# 1-Schematic_polaris_3_3_copy.net
KiCad netlist of a schematic drawn in EasyEDA
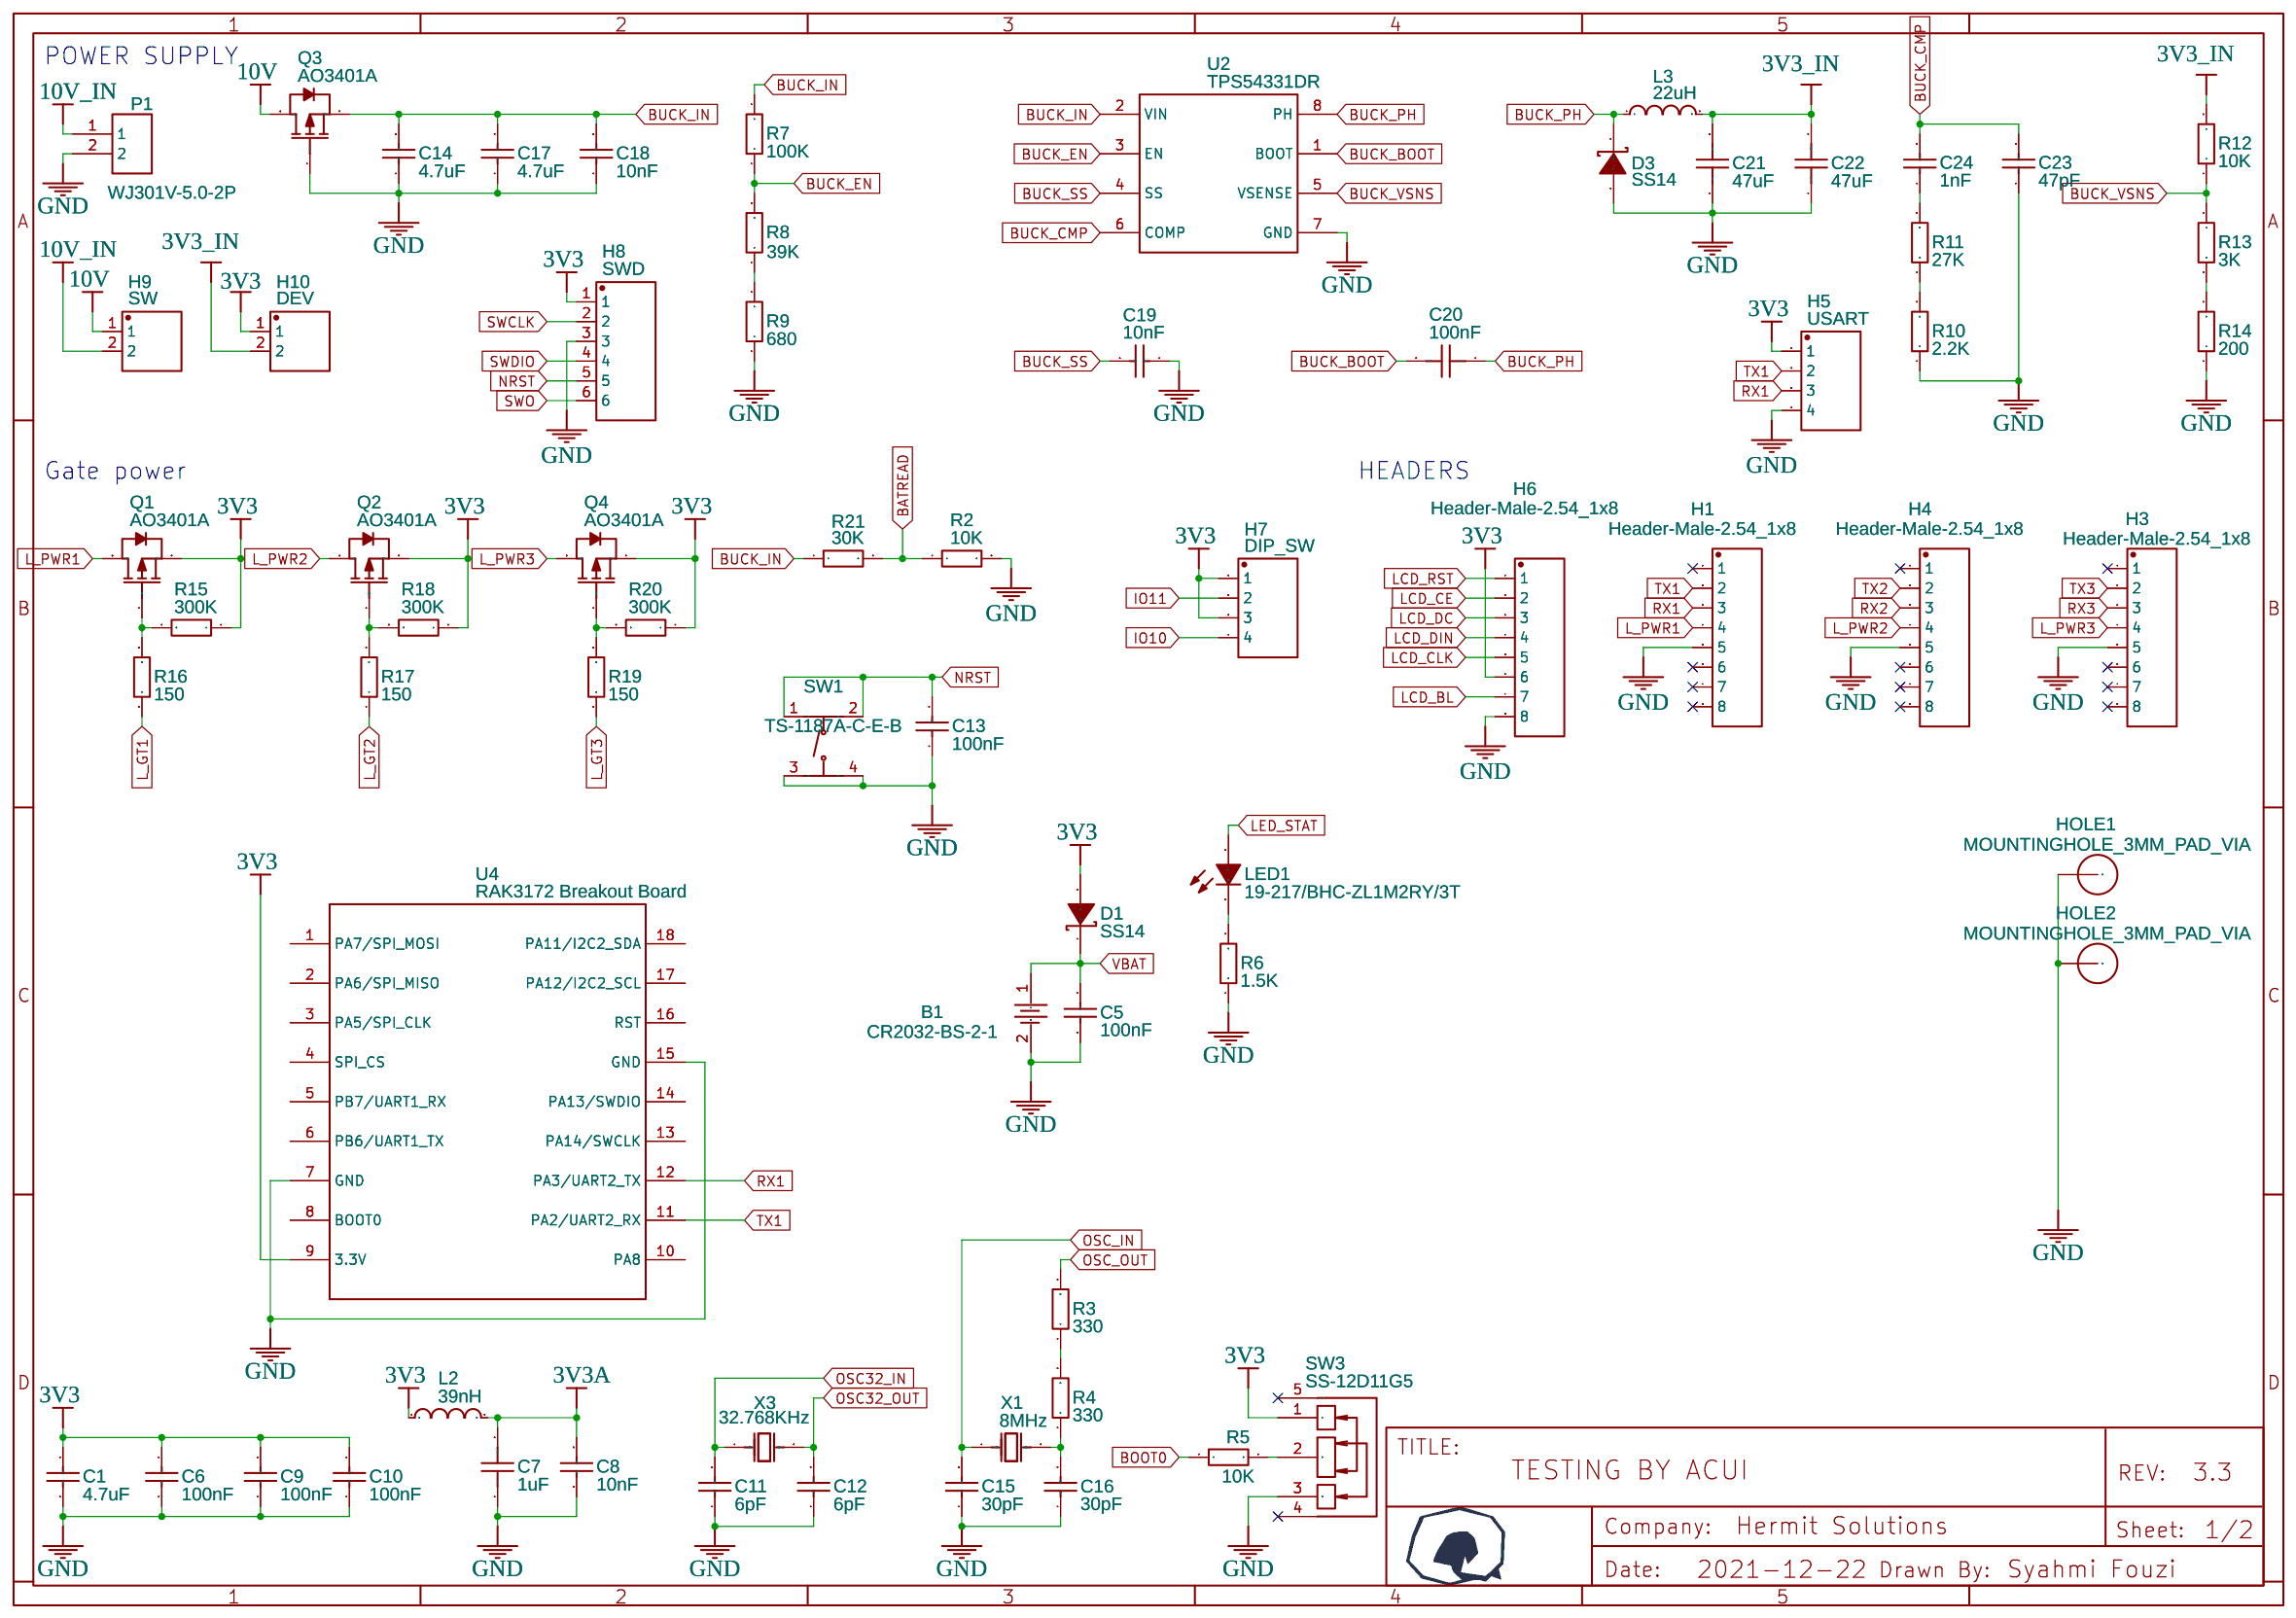
[diagram p0: S_3.3_1.2 copy]
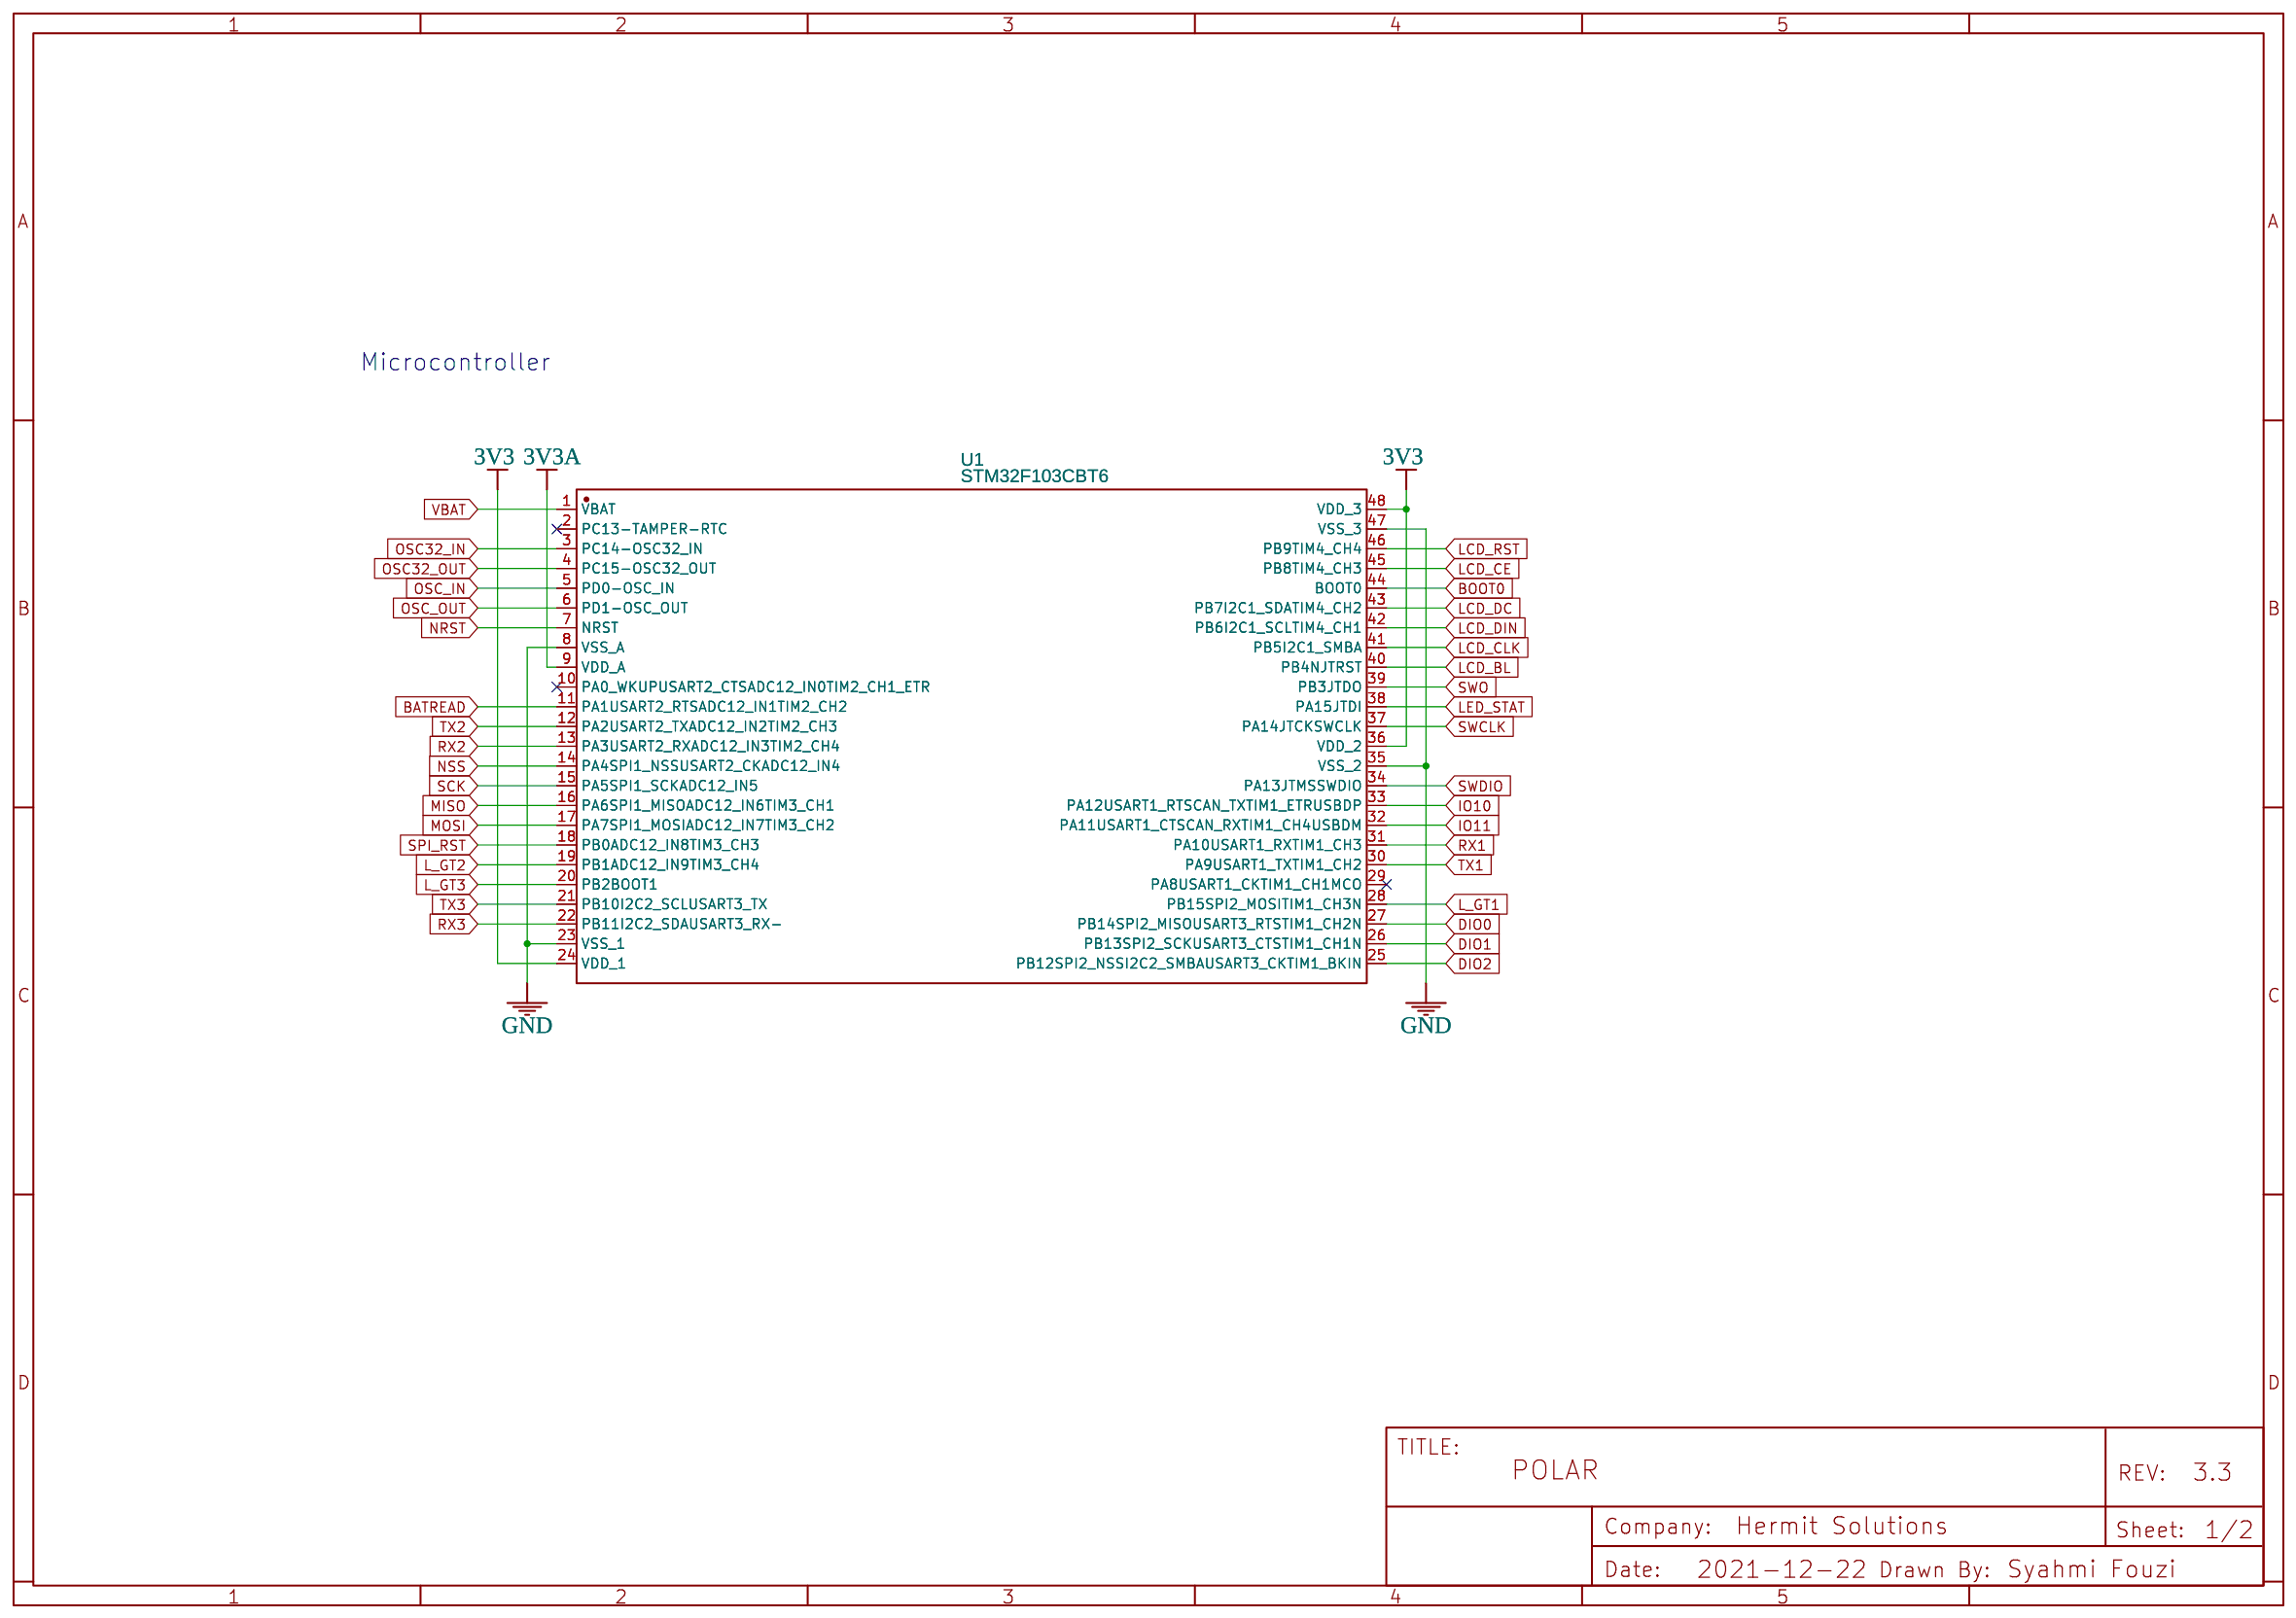
[diagram p1: S_3.3_2.2 copy]

(export (version "E")
  (design (tool "Eeschema 10.0.6"))
  (components
    (comp (ref "B1")
      (value "CR2032-BS-2-1")
      (fields (field (name "BOM_Manufacturer Part") "BS-2-1") (field (name "BOM_Supplier Part") "C70376"))
      (libsource (lib "") (part "CR2032-BS-2-1"))
    )
    (comp (ref "C1")
      (value "4.7uF")
      (fields
        (field (name "BOM_Manufacturer Part") "CL10A475KO8NNNC")
        (field (name "BOM_Supplier Part") "C19666")
      )
      (libsource (lib "") (part "CL10A475KO8NNNC"))
    )
    (comp (ref "C5")
      (value "100nF")
      (fields
        (field (name "BOM_Manufacturer Part") "CC0805KRX7R9BB104")
        (field (name "BOM_Supplier Part") "C49678")
      )
      (libsource (lib "") (part "CC0805KRX7R9BB104"))
    )
    (comp (ref "C6")
      (value "100nF")
      (fields
        (field (name "BOM_Manufacturer Part") "CL05B104KO5NNNC")
        (field (name "BOM_Supplier Part") "C1525")
      )
      (libsource (lib "") (part "CL05B104KO5NNNC"))
    )
    (comp (ref "C7")
      (value "1uF")
      (fields
        (field (name "BOM_Manufacturer Part") "CL05A105KA5NQNC")
        (field (name "BOM_Supplier Part") "C52923")
      )
      (libsource (lib "") (part "CL05A105KA5NQNC"))
    )
    (comp (ref "C8")
      (value "10nF")
      (fields
        (field (name "BOM_Manufacturer Part") "CL05B103KB5NNNC")
        (field (name "BOM_Supplier Part") "C15195")
      )
      (libsource (lib "") (part "CL05B103KB5NNNC"))
    )
    (comp (ref "C9")
      (value "100nF")
      (fields
        (field (name "BOM_Manufacturer Part") "CL05B104KO5NNNC")
        (field (name "BOM_Supplier Part") "C1525")
      )
      (libsource (lib "") (part "CL05B104KO5NNNC"))
    )
    (comp (ref "C10")
      (value "100nF")
      (fields
        (field (name "BOM_Manufacturer Part") "CL05B104KO5NNNC")
        (field (name "BOM_Supplier Part") "C1525")
      )
      (libsource (lib "") (part "CL05B104KO5NNNC"))
    )
    (comp (ref "C11")
      (value "6pF")
      (fields
        (field (name "BOM_Manufacturer Part") "0402CG6R0C500NT")
        (field (name "BOM_Supplier Part") "C30274")
      )
      (libsource (lib "") (part "0402CG6R0C500NT_C30274"))
    )
    (comp (ref "C12")
      (value "6pF")
      (fields
        (field (name "BOM_Manufacturer Part") "0402CG6R0C500NT")
        (field (name "BOM_Supplier Part") "C30274")
      )
      (libsource (lib "") (part "0402CG6R0C500NT_C30274"))
    )
    (comp (ref "C13")
      (value "100nF")
      (fields
        (field (name "BOM_Manufacturer Part") "CL05B104KO5NNNC")
        (field (name "BOM_Supplier Part") "C1525")
      )
      (libsource (lib "") (part "CL05B104KO5NNNC"))
    )
    (comp (ref "C14")
      (value "4.7uF")
      (fields
        (field (name "BOM_Manufacturer Part") "1206B475K500NT")
        (field (name "BOM_Supplier Part") "C29823")
      )
      (libsource (lib "") (part "1206B475K500NT"))
    )
    (comp (ref "C15")
      (value "30pF")
      (fields
        (field (name "BOM_Manufacturer Part") "0402CG300J500NT")
        (field (name "BOM_Supplier Part") "C1570")
      )
      (libsource (lib "") (part "0402CG300J500NT"))
    )
    (comp (ref "C16")
      (value "30pF")
      (fields
        (field (name "BOM_Manufacturer Part") "0402CG300J500NT")
        (field (name "BOM_Supplier Part") "C1570")
      )
      (libsource (lib "") (part "0402CG300J500NT"))
    )
    (comp (ref "C17")
      (value "4.7uF")
      (fields
        (field (name "BOM_Manufacturer Part") "1206B475K500NT")
        (field (name "BOM_Supplier Part") "C29823")
      )
      (libsource (lib "") (part "1206B475K500NT"))
    )
    (comp (ref "C18")
      (value "10nF")
      (fields
        (field (name "BOM_Manufacturer Part") "0603B103K500NT")
        (field (name "BOM_Supplier Part") "C57112")
      )
      (libsource (lib "") (part "0603B103K500NT_1"))
    )
    (comp (ref "C19")
      (value "10nF")
      (fields
        (field (name "BOM_Manufacturer Part") "0603B103K500NT")
        (field (name "BOM_Supplier Part") "C57112")
      )
      (libsource (lib "") (part "0603B103K500NT"))
    )
    (comp (ref "C20")
      (value "100nF")
      (fields
        (field (name "BOM_Manufacturer Part") "CC0603KRX7R9BB104")
        (field (name "BOM_Supplier Part") "C14663")
      )
      (libsource (lib "") (part "CC0603KRX7R9BB104"))
    )
    (comp (ref "C21")
      (value "47uF")
      (fields
        (field (name "BOM_Manufacturer Part") "CL31A476MPHNNNE")
        (field (name "BOM_Supplier Part") "C96123")
      )
      (libsource (lib "") (part "CL31A476MPHNNNE"))
    )
    (comp (ref "C22")
      (value "47uF")
      (fields
        (field (name "BOM_Manufacturer Part") "CL31A476MPHNNNE")
        (field (name "BOM_Supplier Part") "C96123")
      )
      (libsource (lib "") (part "CL31A476MPHNNNE"))
    )
    (comp (ref "C23")
      (value "47pF")
      (fields
        (field (name "BOM_Manufacturer Part") "CL10C470JB8NNNC")
        (field (name "BOM_Supplier Part") "C1671")
      )
      (libsource (lib "") (part "CL10C470JB8NNNC"))
    )
    (comp (ref "C24")
      (value "1nF")
      (fields
        (field (name "BOM_Manufacturer Part") "CL10B102KB8NNNC")
        (field (name "BOM_Supplier Part") "C1588")
      )
      (libsource (lib "") (part "CL10B102KB8NNNC"))
    )
    (comp (ref "D1")
      (value "SS14")
      (fields (field (name "BOM_Supplier Part") "C2480"))
      (libsource (lib "") (part "SS14"))
    )
    (comp (ref "D3")
      (value "SS14")
      (fields (field (name "BOM_Supplier Part") "C2480"))
      (libsource (lib "") (part "SS14_1"))
    )
    (comp (ref "H1")
      (value "Header-Male-2.54_1x8")
      (fields
        (field (name "BOM_Manufacturer Part") "210S-1*8P L=11.6MMGold-plated black")
        (field (name "BOM_Supplier Part") "C124381")
      )
      (libsource (lib "") (part "Header-Male-2.54_1x8"))
    )
    (comp (ref "H3")
      (value "Header-Male-2.54_1x8")
      (fields
        (field (name "BOM_Manufacturer Part") "210S-1*8P L=11.6MMGold-plated black")
        (field (name "BOM_Supplier Part") "C124381")
      )
      (libsource (lib "") (part "Header-Male-2.54_1x8"))
    )
    (comp (ref "H4")
      (value "Header-Male-2.54_1x8")
      (fields
        (field (name "BOM_Manufacturer Part") "210S-1*8P L=11.6MMGold-plated black")
        (field (name "BOM_Supplier Part") "C124381")
      )
      (libsource (lib "") (part "Header-Male-2.54_1x8"))
    )
    (comp (ref "H5")
      (value "USART")
      (fields
        (field (name "BOM_Manufacturer Part") "210S-1*4P L=11.6MMGold-plated black")
        (field (name "BOM_Supplier Part") "C124378")
      )
      (libsource (lib "") (part "Header-Male-2.54_1x4"))
    )
    (comp (ref "H6")
      (value "Header-Male-2.54_1x8")
      (fields
        (field (name "BOM_Manufacturer Part") "210S-1*8P L=11.6MMGold-plated black")
        (field (name "BOM_Supplier Part") "C124381")
      )
      (libsource (lib "") (part "Header-Male-2.54_1x8"))
    )
    (comp (ref "H7")
      (value "DIP_SW")
      (fields
        (field (name "BOM_Manufacturer Part") "210S-1*4P L=11.6MMGold-plated black")
        (field (name "BOM_Supplier Part") "C124378")
      )
      (libsource (lib "") (part "Header-Male-2.54_1x4"))
    )
    (comp (ref "H8")
      (value "SWD")
      (fields
        (field (name "BOM_Manufacturer Part") "210S-1*6P L=11.6MMGold-plated black")
        (field (name "BOM_Supplier Part") "C124380")
      )
      (libsource (lib "") (part "210S-1*6P L=11.6MMGold-plated black"))
    )
    (comp (ref "H9")
      (value "SW")
      (fields
        (field (name "BOM_Manufacturer Part") "210S-1*2P L=11.6MMGold-plated black")
        (field (name "BOM_Supplier Part") "C124375")
      )
      (libsource (lib "") (part "210S-1*2P L=11.6MMGold-plated black"))
    )
    (comp (ref "H10")
      (value "DEV")
      (fields
        (field (name "BOM_Manufacturer Part") "210S-1*2P L=11.6MMGold-plated black")
        (field (name "BOM_Supplier Part") "C124375")
      )
      (libsource (lib "") (part "210S-1*2P L=11.6MMGold-plated black"))
    )
    (comp (ref "HOLE1")
      (value "MOUNTINGHOLE_3MM_PAD_VIA")
      (libsource (lib "") (part "MOUNTINGHOLE_3MM_PAD_VIA"))
    )
    (comp (ref "HOLE2")
      (value "MOUNTINGHOLE_3MM_PAD_VIA")
      (libsource (lib "") (part "MOUNTINGHOLE_3MM_PAD_VIA"))
    )
    (comp (ref "L2")
      (value "39nH")
      (fields
        (field (name "BOM_Manufacturer Part") "SDCL1005C39NJTDF")
        (field (name "BOM_Supplier Part") "C26443")
      )
      (libsource (lib "") (part "SDCL1005C39NJTDF"))
    )
    (comp (ref "L3")
      (value "22uH")
      (fields
        (field (name "BOM_Manufacturer Part") "MWSA1004S-220MT")
        (field (name "BOM_Supplier Part") "C408489")
      )
      (libsource (lib "") (part "MWSA1004S-220MT"))
    )
    (comp (ref "LED1")
      (value "19-217/BHC-ZL1M2RY/3T")
      (fields (field (name "BOM_Supplier Part") "C72041"))
      (libsource (lib "") (part "19-217/BHC-ZL1M2RY/3T"))
    )
    (comp (ref "P1")
      (value "WJ301V-5.0-2P")
      (fields (field (name "BOM_Supplier Part") "C8475"))
      (libsource (lib "") (part "WJ301V-5.0-2P"))
    )
    (comp (ref "Q1")
      (value "AO3401A")
      (fields (field (name "BOM_Supplier Part") "C15127"))
      (libsource (lib "") (part "AO3401A"))
    )
    (comp (ref "Q2")
      (value "AO3401A")
      (fields (field (name "BOM_Supplier Part") "C15127"))
      (libsource (lib "") (part "AO3401A"))
    )
    (comp (ref "Q3")
      (value "AO3401A")
      (fields (field (name "BOM_Supplier Part") "C15127"))
      (libsource (lib "") (part "AO3401A"))
    )
    (comp (ref "Q4")
      (value "AO3401A")
      (fields (field (name "BOM_Supplier Part") "C15127"))
      (libsource (lib "") (part "AO3401A"))
    )
    (comp (ref "R2")
      (value "10K")
      (fields
        (field (name "BOM_Manufacturer Part") "0805W8F1002T5E")
        (field (name "BOM_Supplier Part") "C17414")
      )
      (libsource (lib "") (part "0805W8F1002T5E"))
    )
    (comp (ref "R3")
      (value "330")
      (fields
        (field (name "BOM_Manufacturer Part") "0402WGF3300TCE")
        (field (name "BOM_Supplier Part") "C25104")
      )
      (libsource (lib "") (part "0402WGF3300TCE"))
    )
    (comp (ref "R4")
      (value "330")
      (fields
        (field (name "BOM_Manufacturer Part") "0402WGF3300TCE")
        (field (name "BOM_Supplier Part") "C25104")
      )
      (libsource (lib "") (part "0402WGF3300TCE"))
    )
    (comp (ref "R5")
      (value "10K")
      (fields
        (field (name "BOM_Manufacturer Part") "0402WGF1002TCE")
        (field (name "BOM_Supplier Part") "C25744")
      )
      (libsource (lib "") (part "0402WGF1002TCE"))
    )
    (comp (ref "R6")
      (value "1.5K")
      (fields
        (field (name "BOM_Manufacturer Part") "0603WAF1501T5E")
        (field (name "BOM_Supplier Part") "C22843")
      )
      (libsource (lib "") (part "0603WAF1501T5E"))
    )
    (comp (ref "R7")
      (value "100K")
      (fields
        (field (name "BOM_Manufacturer Part") "0603WAF1003T5E")
        (field (name "BOM_Supplier Part") "C25803")
      )
      (libsource (lib "") (part "0603WAF1003T5E"))
    )
    (comp (ref "R8")
      (value "39K")
      (fields
        (field (name "BOM_Manufacturer Part") "0603WAF3902T5E")
        (field (name "BOM_Supplier Part") "C23153")
      )
      (libsource (lib "") (part "0603WAF3902T5E"))
    )
    (comp (ref "R9")
      (value "680")
      (fields
        (field (name "BOM_Manufacturer Part") "0603WAF6800T5E")
        (field (name "BOM_Supplier Part") "C23228")
      )
      (libsource (lib "") (part "0603WAF6800T5E"))
    )
    (comp (ref "R10")
      (value "2.2K")
      (fields
        (field (name "BOM_Manufacturer Part") "0603WAF2201T5E")
        (field (name "BOM_Supplier Part") "C4190")
      )
      (libsource (lib "") (part "0603WAF2201T5E"))
    )
    (comp (ref "R11")
      (value "27K")
      (fields
        (field (name "BOM_Manufacturer Part") "0603WAF2702T5E")
        (field (name "BOM_Supplier Part") "C22967")
      )
      (libsource (lib "") (part "0603WAF2702T5E"))
    )
    (comp (ref "R12")
      (value "10K")
      (fields
        (field (name "BOM_Manufacturer Part") "0603WAF1002T5E")
        (field (name "BOM_Supplier Part") "C25804")
      )
      (libsource (lib "") (part "0603WAF1002T5E"))
    )
    (comp (ref "R13")
      (value "3K")
      (fields
        (field (name "BOM_Manufacturer Part") "0603WAF3001T5E")
        (field (name "BOM_Supplier Part") "C4211")
      )
      (libsource (lib "") (part "0603WAF3001T5E"))
    )
    (comp (ref "R14")
      (value "200")
      (fields
        (field (name "BOM_Manufacturer Part") "0603WAF2000T5E")
        (field (name "BOM_Supplier Part") "C8218")
      )
      (libsource (lib "") (part "0603WAF2000T5E"))
    )
    (comp (ref "R15")
      (value "300K")
      (fields
        (field (name "BOM_Manufacturer Part") "0402WGF3003TCE")
        (field (name "BOM_Supplier Part") "C25774")
      )
      (libsource (lib "") (part "0402WGF3003TCE"))
    )
    (comp (ref "R16")
      (value "150")
      (fields
        (field (name "BOM_Manufacturer Part") "0402WGF1500TCE")
        (field (name "BOM_Supplier Part") "C25082")
      )
      (libsource (lib "") (part "0402WGF1500TCE"))
    )
    (comp (ref "R17")
      (value "150")
      (fields
        (field (name "BOM_Manufacturer Part") "0402WGF1500TCE")
        (field (name "BOM_Supplier Part") "C25082")
      )
      (libsource (lib "") (part "0402WGF1500TCE"))
    )
    (comp (ref "R18")
      (value "300K")
      (fields
        (field (name "BOM_Manufacturer Part") "0402WGF3003TCE")
        (field (name "BOM_Supplier Part") "C25774")
      )
      (libsource (lib "") (part "0402WGF3003TCE"))
    )
    (comp (ref "R19")
      (value "150")
      (fields
        (field (name "BOM_Manufacturer Part") "0402WGF1500TCE")
        (field (name "BOM_Supplier Part") "C25082")
      )
      (libsource (lib "") (part "0402WGF1500TCE"))
    )
    (comp (ref "R20")
      (value "300K")
      (fields
        (field (name "BOM_Manufacturer Part") "0402WGF3003TCE")
        (field (name "BOM_Supplier Part") "C25774")
      )
      (libsource (lib "") (part "0402WGF3003TCE"))
    )
    (comp (ref "R21")
      (value "30K")
      (fields
        (field (name "BOM_Manufacturer Part") "0805W8F3002T5E")
        (field (name "BOM_Supplier Part") "C17621")
      )
      (libsource (lib "") (part "0805W8F3002T5E"))
    )
    (comp (ref "SW1")
      (value "TS-1187A-C-E-B")
      (fields (field (name "BOM_Supplier Part") "C318887"))
      (libsource (lib "") (part "TS-1187A-C-E-B"))
    )
    (comp (ref "SW3")
      (value "SS-12D11G5")
      (fields (field (name "BOM_Supplier Part") "C692484"))
      (libsource (lib "") (part "SS-12D11G5"))
    )
    (comp (ref "U2")
      (value "TPS54331DR")
      (fields (field (name "BOM_Supplier Part") "C9865"))
      (libsource (lib "") (part "TPS54331DR"))
    )
    (comp (ref "U4")
      (value "RAK3172 Breakout Board")
      (fields (field (name "BOM_Manufacturer Part") "316025") (field (name "BOM_Supplier Part") "RAK3272S"))
      (libsource (lib "") (part "RAK3172 Breakout Board"))
    )
    (comp (ref "X1")
      (value "8MHz")
      (fields
        (field (name "BOM_Manufacturer Part") "X50328MSB2GI")
        (field (name "BOM_Supplier Part") "C115962")
      )
      (libsource (lib "") (part "X50328MSB2GI"))
    )
    (comp (ref "X3")
      (value "32.768KHz")
      (fields
        (field (name "BOM_Manufacturer Part") "FC-12M32.768KHZ7PF20PPM")
        (field (name "BOM_Supplier Part") "C99009")
      )
      (libsource (lib "") (part "FC-12M32.768KHZ7PF20PPM"))
    )
    (comp (ref "U1")
      (value "STM32F103CBT6")
      (fields (field (name "BOM_Supplier Part") "C8304"))
      (libsource (lib "") (part "STM32F103CBT6"))
    )
  )
  (nets
    (net (code "1") (name "3V3") (class "Default")
      (node (ref "C1") (pin "2") (pinfunction "2_2") (pintype "input"))
      (node (ref "C10") (pin "2") (pinfunction "2_2") (pintype "input"))
      (node (ref "C6") (pin "2") (pinfunction "2_2") (pintype "input"))
      (node (ref "C9") (pin "2") (pinfunction "2_2") (pintype "input"))
      (node (ref "D1") (pin "2") (pinfunction "A_2") (pintype "unspecified"))
      (node (ref "H10") (pin "1") (pinfunction "1_1") (pintype "unspecified"))
      (node (ref "H5") (pin "1") (pinfunction "1_1") (pintype "unspecified"))
      (node (ref "H6") (pin "6") (pinfunction "6_6") (pintype "unspecified"))
      (node (ref "H7") (pin "1") (pinfunction "1_1") (pintype "unspecified"))
      (node (ref "H7") (pin "3") (pinfunction "3_3") (pintype "unspecified"))
      (node (ref "H8") (pin "1") (pinfunction "1_1") (pintype "unspecified"))
      (node (ref "L2") (pin "1") (pinfunction "1_1") (pintype "unspecified"))
      (node (ref "Q1") (pin "2") (pinfunction "S_2") (pintype "unspecified"))
      (node (ref "Q2") (pin "2") (pinfunction "S_2") (pintype "unspecified"))
      (node (ref "Q4") (pin "2") (pinfunction "S_2") (pintype "unspecified"))
      (node (ref "R15") (pin "1") (pinfunction "1_1") (pintype "input"))
      (node (ref "R18") (pin "1") (pinfunction "1_1") (pintype "input"))
      (node (ref "R20") (pin "1") (pinfunction "1_1") (pintype "input"))
      (node (ref "SW3") (pin "1") (pinfunction "1_1") (pintype "unspecified"))
      (node (ref "U1") (pin "24") (pinfunction "VDD_1_24") (pintype "unspecified"))
      (node (ref "U1") (pin "36") (pinfunction "VDD_2_36") (pintype "unspecified"))
      (node (ref "U1") (pin "48") (pinfunction "VDD_3_48") (pintype "unspecified"))
      (node (ref "U4") (pin "9") (pinfunction "3.3V_9") (pintype "passive"))
    )
    (net (code "2") (name "3V3A") (class "Default")
      (node (ref "C7") (pin "2") (pinfunction "2_2") (pintype "unspecified"))
      (node (ref "C8") (pin "2") (pinfunction "2_2") (pintype "input"))
      (node (ref "L2") (pin "2") (pinfunction "2_2") (pintype "unspecified"))
      (node (ref "U1") (pin "9") (pinfunction "VDD_A_9") (pintype "unspecified"))
    )
    (net (code "3") (name "3V3_IN") (class "Default")
      (node (ref "C21") (pin "2") (pinfunction "2_2") (pintype "unspecified"))
      (node (ref "C22") (pin "2") (pinfunction "2_2") (pintype "unspecified"))
      (node (ref "H10") (pin "2") (pinfunction "2_2") (pintype "unspecified"))
      (node (ref "L3") (pin "2") (pinfunction "2_2") (pintype "unspecified"))
      (node (ref "R12") (pin "2") (pinfunction "2_2") (pintype "input"))
    )
    (net (code "4") (name "10V") (class "Default")
      (node (ref "H9") (pin "1") (pinfunction "1_1") (pintype "unspecified"))
      (node (ref "Q3") (pin "3") (pinfunction "D_3") (pintype "unspecified"))
    )
    (net (code "5") (name "10V_IN") (class "Default")
      (node (ref "H9") (pin "2") (pinfunction "2_2") (pintype "unspecified"))
      (node (ref "P1") (pin "1") (pinfunction "1_1") (pintype "unspecified"))
    )
    (net (code "6") (name "BATREAD") (class "Default")
      (node (ref "R2") (pin "1") (pinfunction "1_1") (pintype "input"))
      (node (ref "R21") (pin "2") (pinfunction "2_2") (pintype "input"))
      (node (ref "U1") (pin "11") (pinfunction "PA1USART2_RTSADC12_IN1TIM2_CH2_11") (pintype "unspecified"))
    )
    (net (code "7") (name "BOOT0") (class "Default")
      (node (ref "R5") (pin "1") (pinfunction "1_1") (pintype "input"))
      (node (ref "U1") (pin "44") (pinfunction "BOOT0_44") (pintype "unspecified"))
    )
    (net (code "8") (name "BUCK_BOOT") (class "Default")
      (node (ref "C20") (pin "2") (pinfunction "2_2") (pintype "unspecified"))
      (node (ref "U2") (pin "1") (pinfunction "BOOT_1") (pintype "unspecified"))
    )
    (net (code "9") (name "BUCK_CMP") (class "Default")
      (node (ref "C23") (pin "2") (pinfunction "2_2") (pintype "input"))
      (node (ref "C24") (pin "2") (pinfunction "2_2") (pintype "input"))
      (node (ref "U2") (pin "6") (pinfunction "COMP_6") (pintype "unspecified"))
    )
    (net (code "10") (name "BUCK_EN") (class "Default")
      (node (ref "R7") (pin "1") (pinfunction "1_1") (pintype "input"))
      (node (ref "R8") (pin "2") (pinfunction "2_2") (pintype "input"))
      (node (ref "U2") (pin "3") (pinfunction "EN_3") (pintype "unspecified"))
    )
    (net (code "11") (name "BUCK_IN") (class "Default")
      (node (ref "C14") (pin "2") (pinfunction "2_2") (pintype "input"))
      (node (ref "C17") (pin "2") (pinfunction "2_2") (pintype "input"))
      (node (ref "C18") (pin "2") (pinfunction "2_2") (pintype "input"))
      (node (ref "Q3") (pin "2") (pinfunction "S_2") (pintype "unspecified"))
      (node (ref "R21") (pin "1") (pinfunction "1_1") (pintype "input"))
      (node (ref "R7") (pin "2") (pinfunction "2_2") (pintype "input"))
      (node (ref "U2") (pin "2") (pinfunction "VIN_2") (pintype "passive"))
    )
    (net (code "12") (name "BUCK_PH") (class "Default")
      (node (ref "C20") (pin "1") (pinfunction "1_1") (pintype "unspecified"))
      (node (ref "D3") (pin "1") (pinfunction "K_1") (pintype "unspecified"))
      (node (ref "L3") (pin "1") (pinfunction "1_1") (pintype "unspecified"))
      (node (ref "U2") (pin "8") (pinfunction "PH_8") (pintype "passive"))
    )
    (net (code "13") (name "BUCK_SS") (class "Default")
      (node (ref "C19") (pin "2") (pinfunction "2_2") (pintype "input"))
      (node (ref "U2") (pin "4") (pinfunction "SS_4") (pintype "unspecified"))
    )
    (net (code "14") (name "BUCK_VSNS") (class "Default")
      (node (ref "R12") (pin "1") (pinfunction "1_1") (pintype "input"))
      (node (ref "R13") (pin "1") (pinfunction "1_1") (pintype "input"))
      (node (ref "U2") (pin "5") (pinfunction "VSENSE_5") (pintype "unspecified"))
    )
    (net (code "15") (name "DIO0") (class "Default")
      (node (ref "U1") (pin "27") (pinfunction "PB14SPI2_MISOUSART3_RTSTIM1_CH2N_27") (pintype "unspecified"))
    )
    (net (code "16") (name "DIO1") (class "Default")
      (node (ref "U1") (pin "26") (pinfunction "PB13SPI2_SCKUSART3_CTSTIM1_CH1N_26") (pintype "unspecified"))
    )
    (net (code "17") (name "DIO2") (class "Default")
      (node (ref "U1") (pin "25") (pinfunction "PB12SPI2_NSSI2C2_SMBAUSART3_CKTIM1_BKIN_25") (pintype "unspecified"))
    )
    (net (code "18") (name "GND") (class "Default")
      (node (ref "B1") (pin "2") (pinfunction "2_2") (pintype "input"))
      (node (ref "C1") (pin "1") (pinfunction "1_1") (pintype "input"))
      (node (ref "C10") (pin "1") (pinfunction "1_1") (pintype "input"))
      (node (ref "C11") (pin "1") (pinfunction "1_1") (pintype "input"))
      (node (ref "C12") (pin "1") (pinfunction "1_1") (pintype "input"))
      (node (ref "C13") (pin "1") (pinfunction "1_1") (pintype "input"))
      (node (ref "C14") (pin "1") (pinfunction "1_1") (pintype "input"))
      (node (ref "C15") (pin "1") (pinfunction "1_1") (pintype "input"))
      (node (ref "C16") (pin "1") (pinfunction "1_1") (pintype "input"))
      (node (ref "C17") (pin "1") (pinfunction "1_1") (pintype "input"))
      (node (ref "C18") (pin "1") (pinfunction "1_1") (pintype "input"))
      (node (ref "C19") (pin "1") (pinfunction "1_1") (pintype "input"))
      (node (ref "C21") (pin "1") (pinfunction "1_1") (pintype "unspecified"))
      (node (ref "C22") (pin "1") (pinfunction "1_1") (pintype "unspecified"))
      (node (ref "C23") (pin "1") (pinfunction "1_1") (pintype "input"))
      (node (ref "C5") (pin "1") (pinfunction "1_1") (pintype "input"))
      (node (ref "C6") (pin "1") (pinfunction "1_1") (pintype "input"))
      (node (ref "C7") (pin "1") (pinfunction "1_1") (pintype "unspecified"))
      (node (ref "C8") (pin "1") (pinfunction "1_1") (pintype "input"))
      (node (ref "C9") (pin "1") (pinfunction "1_1") (pintype "input"))
      (node (ref "D3") (pin "2") (pinfunction "A_2") (pintype "unspecified"))
      (node (ref "H1") (pin "5") (pinfunction "5_5") (pintype "unspecified"))
      (node (ref "H3") (pin "5") (pinfunction "5_5") (pintype "unspecified"))
      (node (ref "H4") (pin "5") (pinfunction "5_5") (pintype "unspecified"))
      (node (ref "H5") (pin "4") (pinfunction "4_4") (pintype "unspecified"))
      (node (ref "H6") (pin "8") (pinfunction "8_8") (pintype "unspecified"))
      (node (ref "H8") (pin "3") (pinfunction "3_3") (pintype "unspecified"))
      (node (ref "HOLE1") (pin "1") (pinfunction "1_1") (pintype "unspecified"))
      (node (ref "HOLE2") (pin "1") (pinfunction "1_1") (pintype "unspecified"))
      (node (ref "P1") (pin "2") (pinfunction "2_2") (pintype "unspecified"))
      (node (ref "Q3") (pin "1") (pinfunction "G_1") (pintype "unspecified"))
      (node (ref "R10") (pin "1") (pinfunction "1_1") (pintype "input"))
      (node (ref "R14") (pin "1") (pinfunction "1_1") (pintype "input"))
      (node (ref "R2") (pin "2") (pinfunction "2_2") (pintype "input"))
      (node (ref "R6") (pin "1") (pinfunction "1_1") (pintype "input"))
      (node (ref "R9") (pin "1") (pinfunction "1_1") (pintype "input"))
      (node (ref "SW1") (pin "3") (pinfunction "C_3") (pintype "unspecified"))
      (node (ref "SW1") (pin "4") (pinfunction "D_4") (pintype "unspecified"))
      (node (ref "SW3") (pin "3") (pinfunction "3_3") (pintype "unspecified"))
      (node (ref "U1") (pin "23") (pinfunction "VSS_1_23") (pintype "unspecified"))
      (node (ref "U1") (pin "35") (pinfunction "VSS_2_35") (pintype "unspecified"))
      (node (ref "U1") (pin "47") (pinfunction "VSS_3_47") (pintype "unspecified"))
      (node (ref "U1") (pin "8") (pinfunction "VSS_A_8") (pintype "unspecified"))
      (node (ref "U2") (pin "7") (pinfunction "GND_7") (pintype "passive"))
      (node (ref "U4") (pin "15") (pinfunction "GND_15") (pintype "passive"))
      (node (ref "U4") (pin "7") (pinfunction "GND_7") (pintype "passive"))
    )
    (net (code "19") (name "IO10") (class "Default")
      (node (ref "H7") (pin "4") (pinfunction "4_4") (pintype "unspecified"))
      (node (ref "U1") (pin "33") (pinfunction "PA12USART1_RTSCAN_TXTIM1_ETRUSBDP_33") (pintype "unspecified"))
    )
    (net (code "20") (name "IO11") (class "Default")
      (node (ref "H7") (pin "2") (pinfunction "2_2") (pintype "unspecified"))
      (node (ref "U1") (pin "32") (pinfunction "PA11USART1_CTSCAN_RXTIM1_CH4USBDM_32") (pintype "unspecified"))
    )
    (net (code "21") (name "LCD_BL") (class "Default")
      (node (ref "H6") (pin "7") (pinfunction "7_7") (pintype "unspecified"))
      (node (ref "U1") (pin "40") (pinfunction "PB4NJTRST_40") (pintype "unspecified"))
    )
    (net (code "22") (name "LCD_CE") (class "Default")
      (node (ref "H6") (pin "2") (pinfunction "2_2") (pintype "unspecified"))
      (node (ref "U1") (pin "45") (pinfunction "PB8TIM4_CH3_45") (pintype "unspecified"))
    )
    (net (code "23") (name "LCD_CLK") (class "Default")
      (node (ref "H6") (pin "5") (pinfunction "5_5") (pintype "unspecified"))
      (node (ref "U1") (pin "41") (pinfunction "PB5I2C1_SMBA_41") (pintype "unspecified"))
    )
    (net (code "24") (name "LCD_DC") (class "Default")
      (node (ref "H6") (pin "3") (pinfunction "3_3") (pintype "unspecified"))
      (node (ref "U1") (pin "43") (pinfunction "PB7I2C1_SDATIM4_CH2_43") (pintype "unspecified"))
    )
    (net (code "25") (name "LCD_DIN") (class "Default")
      (node (ref "H6") (pin "4") (pinfunction "4_4") (pintype "unspecified"))
      (node (ref "U1") (pin "42") (pinfunction "PB6I2C1_SCLTIM4_CH1_42") (pintype "unspecified"))
    )
    (net (code "26") (name "LCD_RST") (class "Default")
      (node (ref "H6") (pin "1") (pinfunction "1_1") (pintype "unspecified"))
      (node (ref "U1") (pin "46") (pinfunction "PB9TIM4_CH4_46") (pintype "unspecified"))
    )
    (net (code "27") (name "LED_STAT") (class "Default")
      (node (ref "LED1") (pin "1") (pinfunction "A_1") (pintype "input"))
      (node (ref "U1") (pin "38") (pinfunction "PA15JTDI_38") (pintype "unspecified"))
    )
    (net (code "28") (name "L_GT1") (class "Default")
      (node (ref "R16") (pin "1") (pinfunction "1_1") (pintype "input"))
      (node (ref "U1") (pin "28") (pinfunction "PB15SPI2_MOSITIM1_CH3N_28") (pintype "unspecified"))
    )
    (net (code "29") (name "L_GT2") (class "Default")
      (node (ref "R17") (pin "1") (pinfunction "1_1") (pintype "input"))
      (node (ref "U1") (pin "19") (pinfunction "PB1ADC12_IN9TIM3_CH4_19") (pintype "unspecified"))
    )
    (net (code "30") (name "L_GT3") (class "Default")
      (node (ref "R19") (pin "1") (pinfunction "1_1") (pintype "input"))
      (node (ref "U1") (pin "20") (pinfunction "PB2BOOT1_20") (pintype "unspecified"))
    )
    (net (code "31") (name "L_PWR1") (class "Default")
      (node (ref "H1") (pin "4") (pinfunction "4_4") (pintype "unspecified"))
      (node (ref "Q1") (pin "3") (pinfunction "D_3") (pintype "unspecified"))
    )
    (net (code "32") (name "L_PWR2") (class "Default")
      (node (ref "H4") (pin "4") (pinfunction "4_4") (pintype "unspecified"))
      (node (ref "Q2") (pin "3") (pinfunction "D_3") (pintype "unspecified"))
    )
    (net (code "33") (name "L_PWR3") (class "Default")
      (node (ref "H3") (pin "4") (pinfunction "4_4") (pintype "unspecified"))
      (node (ref "Q4") (pin "3") (pinfunction "D_3") (pintype "unspecified"))
    )
    (net (code "34") (name "MISO") (class "Default")
      (node (ref "U1") (pin "16") (pinfunction "PA6SPI1_MISOADC12_IN6TIM3_CH1_16") (pintype "unspecified"))
    )
    (net (code "35") (name "MOSI") (class "Default")
      (node (ref "U1") (pin "17") (pinfunction "PA7SPI1_MOSIADC12_IN7TIM3_CH2_17") (pintype "unspecified"))
    )
    (net (code "36") (name "NRST") (class "Default")
      (node (ref "C13") (pin "2") (pinfunction "2_2") (pintype "input"))
      (node (ref "H8") (pin "5") (pinfunction "5_5") (pintype "unspecified"))
      (node (ref "SW1") (pin "1") (pinfunction "A_1") (pintype "unspecified"))
      (node (ref "SW1") (pin "2") (pinfunction "B_2") (pintype "unspecified"))
      (node (ref "U1") (pin "7") (pinfunction "NRST_7") (pintype "unspecified"))
    )
    (net (code "37") (name "NSS") (class "Default")
      (node (ref "U1") (pin "14") (pinfunction "PA4SPI1_NSSUSART2_CKADC12_IN4_14") (pintype "unspecified"))
    )
    (net (code "38") (name "Net-(C24-Pad1)") (class "Default")
      (node (ref "C24") (pin "1") (pinfunction "1_1") (pintype "input"))
      (node (ref "R11") (pin "2") (pinfunction "2_2") (pintype "input"))
    )
    (net (code "39") (name "Net-(LED1-C)") (class "Default")
      (node (ref "LED1") (pin "2") (pinfunction "C_2") (pintype "input"))
      (node (ref "R6") (pin "2") (pinfunction "2_2") (pintype "input"))
    )
    (net (code "40") (name "Net-(Q1-G)") (class "Default")
      (node (ref "Q1") (pin "1") (pinfunction "G_1") (pintype "unspecified"))
      (node (ref "R15") (pin "2") (pinfunction "2_2") (pintype "input"))
      (node (ref "R16") (pin "2") (pinfunction "2_2") (pintype "input"))
    )
    (net (code "41") (name "Net-(Q2-G)") (class "Default")
      (node (ref "Q2") (pin "1") (pinfunction "G_1") (pintype "unspecified"))
      (node (ref "R17") (pin "2") (pinfunction "2_2") (pintype "input"))
      (node (ref "R18") (pin "2") (pinfunction "2_2") (pintype "input"))
    )
    (net (code "42") (name "Net-(Q4-G)") (class "Default")
      (node (ref "Q4") (pin "1") (pinfunction "G_1") (pintype "unspecified"))
      (node (ref "R19") (pin "2") (pinfunction "2_2") (pintype "input"))
      (node (ref "R20") (pin "2") (pinfunction "2_2") (pintype "input"))
    )
    (net (code "43") (name "Net-(R3-Pad1)") (class "Default")
      (node (ref "R3") (pin "1") (pinfunction "1_1") (pintype "input"))
      (node (ref "R4") (pin "2") (pinfunction "2_2") (pintype "input"))
    )
    (net (code "44") (name "Net-(R5-Pad2)") (class "Default")
      (node (ref "R5") (pin "2") (pinfunction "2_2") (pintype "input"))
      (node (ref "SW3") (pin "2") (pinfunction "2_2") (pintype "unspecified"))
    )
    (net (code "45") (name "Net-(R8-Pad1)") (class "Default")
      (node (ref "R8") (pin "1") (pinfunction "1_1") (pintype "input"))
      (node (ref "R9") (pin "2") (pinfunction "2_2") (pintype "input"))
    )
    (net (code "46") (name "Net-(R10-Pad2)") (class "Default")
      (node (ref "R10") (pin "2") (pinfunction "2_2") (pintype "input"))
      (node (ref "R11") (pin "1") (pinfunction "1_1") (pintype "input"))
    )
    (net (code "47") (name "Net-(R13-Pad2)") (class "Default")
      (node (ref "R13") (pin "2") (pinfunction "2_2") (pintype "input"))
      (node (ref "R14") (pin "2") (pinfunction "2_2") (pintype "input"))
    )
    (net (code "48") (name "Net-(X1-OSC2)") (class "Default")
      (node (ref "C16") (pin "2") (pinfunction "2_2") (pintype "input"))
      (node (ref "R4") (pin "1") (pinfunction "1_1") (pintype "input"))
      (node (ref "X1") (pin "2") (pinfunction "OSC2_2") (pintype "input"))
    )
    (net (code "49") (name "OSC32_IN") (class "Default")
      (node (ref "C11") (pin "2") (pinfunction "2_2") (pintype "input"))
      (node (ref "U1") (pin "3") (pinfunction "PC14-OSC32_IN_3") (pintype "unspecified"))
      (node (ref "X3") (pin "1") (pinfunction "OSC1_1") (pintype "input"))
    )
    (net (code "50") (name "OSC32_OUT") (class "Default")
      (node (ref "C12") (pin "2") (pinfunction "2_2") (pintype "input"))
      (node (ref "U1") (pin "4") (pinfunction "PC15-OSC32_OUT_4") (pintype "unspecified"))
      (node (ref "X3") (pin "2") (pinfunction "OSC2_2") (pintype "input"))
    )
    (net (code "51") (name "OSC_IN") (class "Default")
      (node (ref "C15") (pin "2") (pinfunction "2_2") (pintype "input"))
      (node (ref "U1") (pin "5") (pinfunction "PD0-OSC_IN_5") (pintype "unspecified"))
      (node (ref "X1") (pin "1") (pinfunction "OSC1_1") (pintype "input"))
    )
    (net (code "52") (name "OSC_OUT") (class "Default")
      (node (ref "R3") (pin "2") (pinfunction "2_2") (pintype "input"))
      (node (ref "U1") (pin "6") (pinfunction "PD1-OSC_OUT_6") (pintype "unspecified"))
    )
    (net (code "53") (name "RX1") (class "Default")
      (node (ref "H1") (pin "3") (pinfunction "3_3") (pintype "unspecified"))
      (node (ref "H5") (pin "3") (pinfunction "3_3") (pintype "unspecified"))
      (node (ref "U1") (pin "31") (pinfunction "PA10USART1_RXTIM1_CH3_31") (pintype "unspecified"))
      (node (ref "U4") (pin "12") (pinfunction "PA3/UART2_TX_12") (pintype "bidirectional"))
    )
    (net (code "54") (name "RX2") (class "Default")
      (node (ref "H4") (pin "3") (pinfunction "3_3") (pintype "unspecified"))
      (node (ref "U1") (pin "13") (pinfunction "PA3USART2_RXADC12_IN3TIM2_CH4_13") (pintype "unspecified"))
    )
    (net (code "55") (name "RX3") (class "Default")
      (node (ref "H3") (pin "3") (pinfunction "3_3") (pintype "unspecified"))
      (node (ref "U1") (pin "22") (pinfunction "PB11I2C2_SDAUSART3_RX-_22") (pintype "unspecified"))
    )
    (net (code "56") (name "SCK") (class "Default")
      (node (ref "U1") (pin "15") (pinfunction "PA5SPI1_SCKADC12_IN5_15") (pintype "unspecified"))
    )
    (net (code "57") (name "SPI_RST") (class "Default")
      (node (ref "U1") (pin "18") (pinfunction "PB0ADC12_IN8TIM3_CH3_18") (pintype "unspecified"))
    )
    (net (code "58") (name "SWCLK") (class "Default")
      (node (ref "H8") (pin "2") (pinfunction "2_2") (pintype "unspecified"))
      (node (ref "U1") (pin "37") (pinfunction "PA14JTCKSWCLK_37") (pintype "unspecified"))
    )
    (net (code "59") (name "SWDIO") (class "Default")
      (node (ref "H8") (pin "4") (pinfunction "4_4") (pintype "unspecified"))
      (node (ref "U1") (pin "34") (pinfunction "PA13JTMSSWDIO_34") (pintype "unspecified"))
    )
    (net (code "60") (name "SWO") (class "Default")
      (node (ref "H8") (pin "6") (pinfunction "6_6") (pintype "unspecified"))
      (node (ref "U1") (pin "39") (pinfunction "PB3JTDO_39") (pintype "unspecified"))
    )
    (net (code "61") (name "TX1") (class "Default")
      (node (ref "H1") (pin "2") (pinfunction "2_2") (pintype "unspecified"))
      (node (ref "H5") (pin "2") (pinfunction "2_2") (pintype "unspecified"))
      (node (ref "U1") (pin "30") (pinfunction "PA9USART1_TXTIM1_CH2_30") (pintype "unspecified"))
      (node (ref "U4") (pin "11") (pinfunction "PA2/UART2_RX_11") (pintype "bidirectional"))
    )
    (net (code "62") (name "TX2") (class "Default")
      (node (ref "H4") (pin "2") (pinfunction "2_2") (pintype "unspecified"))
      (node (ref "U1") (pin "12") (pinfunction "PA2USART2_TXADC12_IN2TIM2_CH3_12") (pintype "unspecified"))
    )
    (net (code "63") (name "TX3") (class "Default")
      (node (ref "H3") (pin "2") (pinfunction "2_2") (pintype "unspecified"))
      (node (ref "U1") (pin "21") (pinfunction "PB10I2C2_SCLUSART3_TX_21") (pintype "unspecified"))
    )
    (net (code "64") (name "VBAT") (class "Default")
      (node (ref "B1") (pin "1") (pinfunction "1_1") (pintype "input"))
      (node (ref "C5") (pin "2") (pinfunction "2_2") (pintype "input"))
      (node (ref "D1") (pin "1") (pinfunction "K_1") (pintype "unspecified"))
      (node (ref "U1") (pin "1") (pinfunction "VBAT_1") (pintype "unspecified"))
    )
    (net (code "65") (name "unconnected-(H1-Pad1)") (class "Default")
      (node (ref "H1") (pin "1") (pinfunction "1_1") (pintype "unspecified+no_connect"))
    )
    (net (code "66") (name "unconnected-(H1-Pad6)") (class "Default")
      (node (ref "H1") (pin "6") (pinfunction "6_6") (pintype "unspecified+no_connect"))
    )
    (net (code "67") (name "unconnected-(H1-Pad7)") (class "Default")
      (node (ref "H1") (pin "7") (pinfunction "7_7") (pintype "unspecified+no_connect"))
    )
    (net (code "68") (name "unconnected-(H1-Pad8)") (class "Default")
      (node (ref "H1") (pin "8") (pinfunction "8_8") (pintype "unspecified+no_connect"))
    )
    (net (code "69") (name "unconnected-(H3-Pad1)") (class "Default")
      (node (ref "H3") (pin "1") (pinfunction "1_1") (pintype "unspecified+no_connect"))
    )
    (net (code "70") (name "unconnected-(H3-Pad6)") (class "Default")
      (node (ref "H3") (pin "6") (pinfunction "6_6") (pintype "unspecified+no_connect"))
    )
    (net (code "71") (name "unconnected-(H3-Pad7)") (class "Default")
      (node (ref "H3") (pin "7") (pinfunction "7_7") (pintype "unspecified+no_connect"))
    )
    (net (code "72") (name "unconnected-(H3-Pad8)") (class "Default")
      (node (ref "H3") (pin "8") (pinfunction "8_8") (pintype "unspecified+no_connect"))
    )
    (net (code "73") (name "unconnected-(H4-Pad1)") (class "Default")
      (node (ref "H4") (pin "1") (pinfunction "1_1") (pintype "unspecified+no_connect"))
    )
    (net (code "74") (name "unconnected-(H4-Pad6)") (class "Default")
      (node (ref "H4") (pin "6") (pinfunction "6_6") (pintype "unspecified+no_connect"))
    )
    (net (code "75") (name "unconnected-(H4-Pad7)") (class "Default")
      (node (ref "H4") (pin "7") (pinfunction "7_7") (pintype "unspecified+no_connect"))
    )
    (net (code "76") (name "unconnected-(H4-Pad8)") (class "Default")
      (node (ref "H4") (pin "8") (pinfunction "8_8") (pintype "unspecified+no_connect"))
    )
    (net (code "77") (name "unconnected-(SW3-Pad4)") (class "Default")
      (node (ref "SW3") (pin "4") (pinfunction "4_4") (pintype "unspecified+no_connect"))
    )
    (net (code "78") (name "unconnected-(SW3-Pad5)") (class "Default")
      (node (ref "SW3") (pin "5") (pinfunction "5_5") (pintype "unspecified+no_connect"))
    )
    (net (code "79") (name "unconnected-(U1-PA0_WKUPUSART2_CTSADC12_IN0TIM2_CH1_ETR-Pad10)") (class "Default")
      (node (ref "U1") (pin "10") (pinfunction "PA0_WKUPUSART2_CTSADC12_IN0TIM2_CH1_ETR_10") (pintype "unspecified+no_connect"))
    )
    (net (code "80") (name "unconnected-(U1-PA8USART1_CKTIM1_CH1MCO-Pad29)") (class "Default")
      (node (ref "U1") (pin "29") (pinfunction "PA8USART1_CKTIM1_CH1MCO_29") (pintype "unspecified+no_connect"))
    )
    (net (code "81") (name "unconnected-(U1-PC13-TAMPER-RTC-Pad2)") (class "Default")
      (node (ref "U1") (pin "2") (pinfunction "PC13-TAMPER-RTC_2") (pintype "unspecified+no_connect"))
    )
    (net (code "82") (name "unconnected-(U4-BOOT0-Pad8)") (class "Default")
      (node (ref "U4") (pin "8") (pinfunction "BOOT0_8") (pintype "input"))
    )
    (net (code "83") (name "unconnected-(U4-PA5{slash}SPI_CLK-Pad3)") (class "Default")
      (node (ref "U4") (pin "3") (pinfunction "PA5/SPI_CLK_3") (pintype "bidirectional"))
    )
    (net (code "84") (name "unconnected-(U4-PA6{slash}SPI_MISO-Pad2)") (class "Default")
      (node (ref "U4") (pin "2") (pinfunction "PA6/SPI_MISO_2") (pintype "bidirectional"))
    )
    (net (code "85") (name "unconnected-(U4-PA7{slash}SPI_MOSI-Pad1)") (class "Default")
      (node (ref "U4") (pin "1") (pinfunction "PA7/SPI_MOSI_1") (pintype "bidirectional"))
    )
    (net (code "86") (name "unconnected-(U4-PA8-Pad10)") (class "Default")
      (node (ref "U4") (pin "10") (pinfunction "PA8_10") (pintype "bidirectional"))
    )
    (net (code "87") (name "unconnected-(U4-PA11{slash}I2C2_SDA-Pad18)") (class "Default")
      (node (ref "U4") (pin "18") (pinfunction "PA11/I2C2_SDA_18") (pintype "bidirectional"))
    )
    (net (code "88") (name "unconnected-(U4-PA12{slash}I2C2_SCL-Pad17)") (class "Default")
      (node (ref "U4") (pin "17") (pinfunction "PA12/I2C2_SCL_17") (pintype "bidirectional"))
    )
    (net (code "89") (name "unconnected-(U4-PA13{slash}SWDIO-Pad14)") (class "Default")
      (node (ref "U4") (pin "14") (pinfunction "PA13/SWDIO_14") (pintype "bidirectional"))
    )
    (net (code "90") (name "unconnected-(U4-PA14{slash}SWCLK-Pad13)") (class "Default")
      (node (ref "U4") (pin "13") (pinfunction "PA14/SWCLK_13") (pintype "bidirectional"))
    )
    (net (code "91") (name "unconnected-(U4-PB6{slash}UART1_TX-Pad6)") (class "Default")
      (node (ref "U4") (pin "6") (pinfunction "PB6/UART1_TX_6") (pintype "bidirectional"))
    )
    (net (code "92") (name "unconnected-(U4-PB7{slash}UART1_RX-Pad5)") (class "Default")
      (node (ref "U4") (pin "5") (pinfunction "PB7/UART1_RX_5") (pintype "bidirectional"))
    )
    (net (code "93") (name "unconnected-(U4-RST-Pad16)") (class "Default")
      (node (ref "U4") (pin "16") (pinfunction "RST_16") (pintype "input"))
    )
    (net (code "94") (name "unconnected-(U4-SPI_CS-Pad4)") (class "Default")
      (node (ref "U4") (pin "4") (pinfunction "SPI_CS_4") (pintype "bidirectional"))
    )
  )
)
